# BSU_Comm.net
KiCad netlist of a schematic drawn in Altium Designer
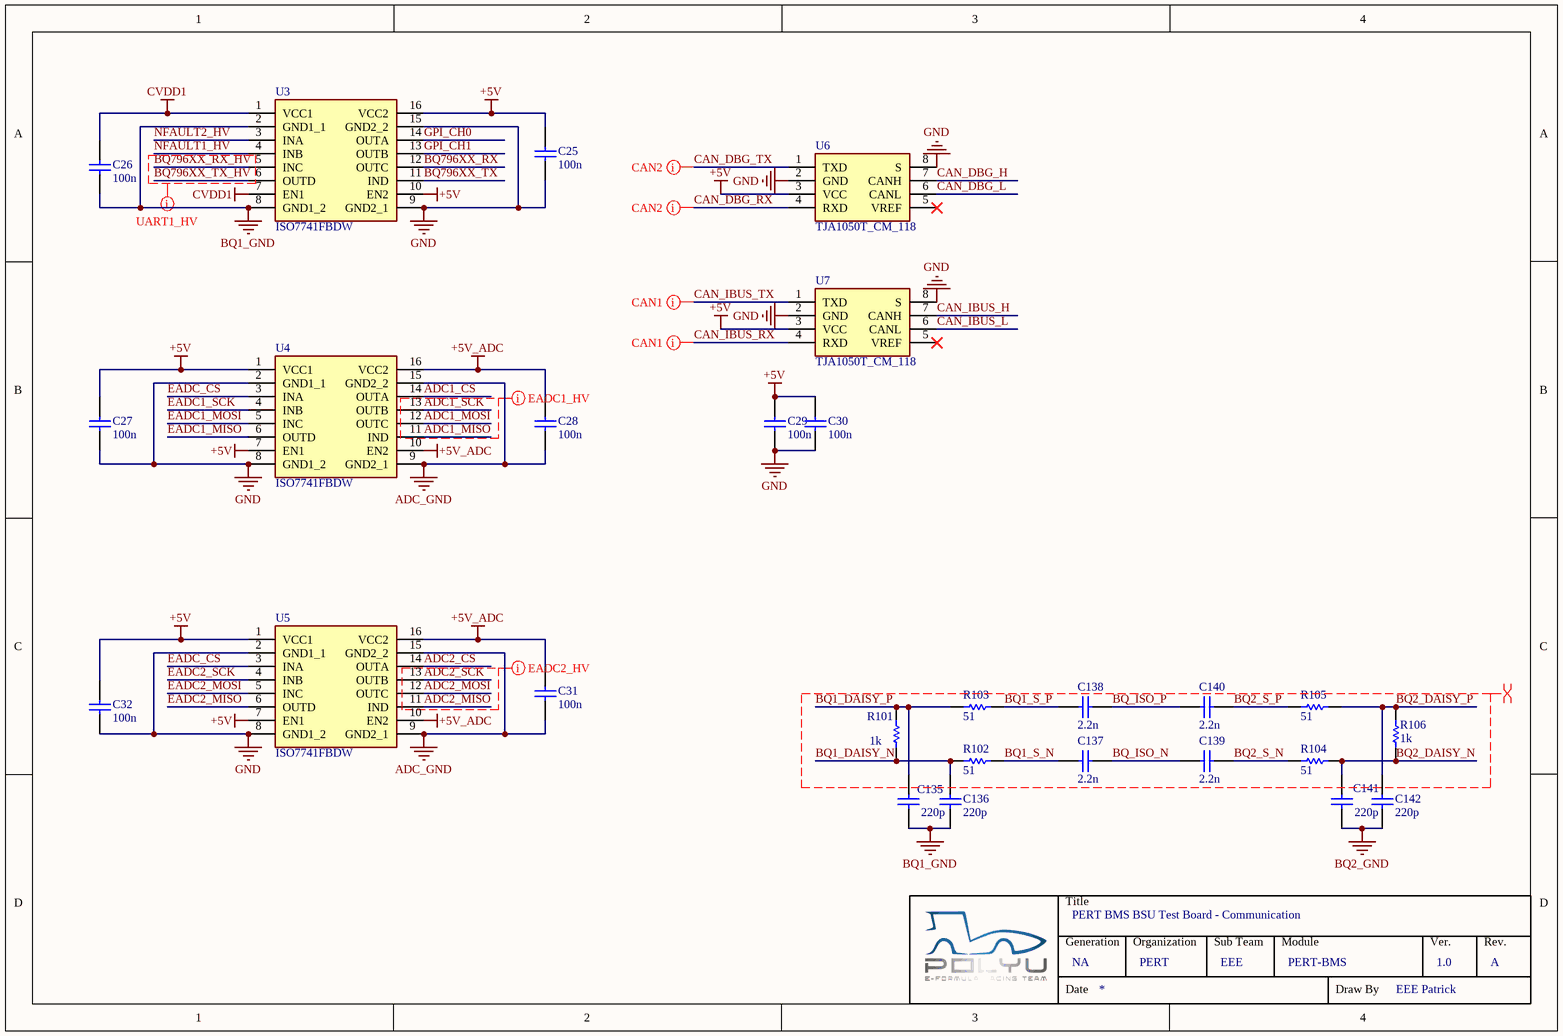
[diagram p0: BSU_Comm.SchDoc]

(export (version "E")
  (design (tool "Eeschema 10.0.6"))
  (components
    (comp (ref "C25")
      (value "100n")
      (footprint "0805_SMD_C")
      (description "0805 SMD Capacitor")
      (libsource (lib "BMS_ShareComponentLibrary") (part "0805_SMD_Capacitor"))
    )
    (comp (ref "C26")
      (value "100n")
      (footprint "0805_SMD_C")
      (description "0805 SMD Capacitor")
      (libsource (lib "BMS_ShareComponentLibrary") (part "0805_SMD_Capacitor"))
    )
    (comp (ref "C27")
      (value "100n")
      (footprint "0805_SMD_C")
      (description "0805 SMD Capacitor")
      (libsource (lib "BMS_ShareComponentLibrary") (part "0805_SMD_Capacitor"))
    )
    (comp (ref "C28")
      (value "100n")
      (footprint "0805_SMD_C")
      (description "0805 SMD Capacitor")
      (libsource (lib "BMS_ShareComponentLibrary") (part "0805_SMD_Capacitor"))
    )
    (comp (ref "C29")
      (value "100n")
      (footprint "0805_SMD_C")
      (description "0805 SMD Capacitor")
      (libsource (lib "BMS_ShareComponentLibrary") (part "0805_SMD_Capacitor"))
    )
    (comp (ref "C30")
      (value "100n")
      (footprint "0805_SMD_C")
      (description "0805 SMD Capacitor")
      (libsource (lib "BMS_ShareComponentLibrary") (part "0805_SMD_Capacitor"))
    )
    (comp (ref "C31")
      (value "100n")
      (footprint "0805_SMD_C")
      (description "0805 SMD Capacitor")
      (libsource (lib "BMS_ShareComponentLibrary") (part "0805_SMD_Capacitor"))
    )
    (comp (ref "C32")
      (value "100n")
      (footprint "0805_SMD_C")
      (description "0805 SMD Capacitor")
      (libsource (lib "BMS_ShareComponentLibrary") (part "0805_SMD_Capacitor"))
    )
    (comp (ref "C135")
      (value "220p")
      (footprint "0603_SMD_C")
      (description "0603 SMD Capacitor")
      (libsource (lib "BMS_ShareComponentLibrary") (part "0603_SMD_Capacitor"))
    )
    (comp (ref "C136")
      (value "220p")
      (footprint "0603_SMD_C")
      (description "0603 SMD Capacitor")
      (libsource (lib "BMS_ShareComponentLibrary") (part "0603_SMD_Capacitor"))
    )
    (comp (ref "C137")
      (value "2.2n")
      (footprint "0603_SMD_C")
      (description "0603 SMD Capacitor")
      (libsource (lib "BMS_ShareComponentLibrary") (part "0603_SMD_Capacitor"))
    )
    (comp (ref "C138")
      (value "2.2n")
      (footprint "0603_SMD_C")
      (description "0603 SMD Capacitor")
      (libsource (lib "BMS_ShareComponentLibrary") (part "0603_SMD_Capacitor"))
    )
    (comp (ref "C139")
      (value "2.2n")
      (footprint "0603_SMD_C")
      (description "0603 SMD Capacitor")
      (libsource (lib "BMS_ShareComponentLibrary") (part "0603_SMD_Capacitor"))
    )
    (comp (ref "C140")
      (value "2.2n")
      (footprint "0603_SMD_C")
      (description "0603 SMD Capacitor")
      (libsource (lib "BMS_ShareComponentLibrary") (part "0603_SMD_Capacitor"))
    )
    (comp (ref "C141")
      (value "220p")
      (footprint "0603_SMD_C")
      (description "0603 SMD Capacitor")
      (libsource (lib "BMS_ShareComponentLibrary") (part "0603_SMD_Capacitor"))
    )
    (comp (ref "C142")
      (value "220p")
      (footprint "0603_SMD_C")
      (description "0603 SMD Capacitor")
      (libsource (lib "BMS_ShareComponentLibrary") (part "0603_SMD_Capacitor"))
    )
    (comp (ref "R101")
      (value "1k")
      (footprint "0603_SMD_R")
      (description "0603 SMD Resistor")
      (libsource (lib "BMS_ShareComponentLibrary") (part "0603_SMD_Resistor"))
    )
    (comp (ref "R102")
      (value "51")
      (footprint "0603_SMD_R")
      (description "0603 SMD Resistor")
      (libsource (lib "BMS_ShareComponentLibrary") (part "0603_SMD_Resistor"))
    )
    (comp (ref "R103")
      (value "51")
      (footprint "0603_SMD_R")
      (description "0603 SMD Resistor")
      (libsource (lib "BMS_ShareComponentLibrary") (part "0603_SMD_Resistor"))
    )
    (comp (ref "R104")
      (value "51")
      (footprint "0603_SMD_R")
      (description "0603 SMD Resistor")
      (libsource (lib "BMS_ShareComponentLibrary") (part "0603_SMD_Resistor"))
    )
    (comp (ref "R105")
      (value "51")
      (footprint "0603_SMD_R")
      (description "0603 SMD Resistor")
      (libsource (lib "BMS_ShareComponentLibrary") (part "0603_SMD_Resistor"))
    )
    (comp (ref "R106")
      (value "1k")
      (footprint "0603_SMD_R")
      (description "0603 SMD Resistor")
      (libsource (lib "BMS_ShareComponentLibrary") (part "0603_SMD_Resistor"))
    )
    (comp (ref "U3")
      (value "ISO7741FBDW")
      (footprint "SOIC16_ISO7741")
      (description "Digital Isolators Robust EMC, quad-channel, 3/1, reinforced digital isolator 16-SOIC -55 to 125")
      (fields (field (name "MOUSER PART NUMBER") "595-ISO7741FBDW"))
      (libsource (lib "BMS_ShareComponentLibrary") (part "ISO7741FBDW"))
    )
    (comp (ref "U4")
      (value "ISO7741FBDW")
      (footprint "SOIC16_ISO7741")
      (description "Digital Isolators Robust EMC, quad-channel, 3/1, reinforced digital isolator 16-SOIC -55 to 125")
      (fields (field (name "MOUSER PART NUMBER") "595-ISO7741FBDW"))
      (libsource (lib "BMS_ShareComponentLibrary") (part "ISO7741FBDW"))
    )
    (comp (ref "U5")
      (value "ISO7741FBDW")
      (footprint "SOIC16_ISO7741")
      (description "Digital Isolators Robust EMC, quad-channel, 3/1, reinforced digital isolator 16-SOIC -55 to 125")
      (fields (field (name "MOUSER PART NUMBER") "595-ISO7741FBDW"))
      (libsource (lib "BMS_ShareComponentLibrary") (part "ISO7741FBDW"))
    )
    (comp (ref "U6")
      (value "TJA1050T_CM_118")
      (footprint "SOIC8_TJA1050")
      (description "NXP - TJA1050T/CM,118 - CAN TRANSCEIVER, 1TX/RX, SOIC-8")
      (fields
        (field (name "MOUSER PART NUMBER") "771-TJA1050T/CM118")
        (field (name "MANUFACTURER_PART_NUMBER") "TJA1050T/CM,118")
      )
      (libsource (lib "BMS_ShareComponentLibrary") (part "TJA1050T"))
    )
    (comp (ref "U7")
      (value "TJA1050T_CM_118")
      (footprint "SOIC8_TJA1050")
      (description "NXP - TJA1050T/CM,118 - CAN TRANSCEIVER, 1TX/RX, SOIC-8")
      (fields
        (field (name "MOUSER PART NUMBER") "771-TJA1050T/CM118")
        (field (name "MANUFACTURER_PART_NUMBER") "TJA1050T/CM,118")
      )
      (libsource (lib "BMS_ShareComponentLibrary") (part "TJA1050T"))
    )
  )
  (nets
    (net (code "1") (name "+5V") (class "Default")
      (node (ref "C25") (pin "2") (pinfunction "2_2") (pintype "passive"))
      (node (ref "C27") (pin "2") (pinfunction "2_2") (pintype "passive"))
      (node (ref "C29") (pin "2") (pinfunction "2_2") (pintype "passive"))
      (node (ref "C30") (pin "2") (pinfunction "2_2") (pintype "passive"))
      (node (ref "C32") (pin "2") (pinfunction "2_2") (pintype "passive"))
      (node (ref "U3") (pin "10") (pinfunction "EN2_10") (pintype "passive"))
      (node (ref "U3") (pin "16") (pinfunction "VCC2_16") (pintype "passive"))
      (node (ref "U4") (pin "1") (pinfunction "VCC1_1") (pintype "passive"))
      (node (ref "U4") (pin "7") (pinfunction "EN1_7") (pintype "passive"))
      (node (ref "U5") (pin "1") (pinfunction "VCC1_1") (pintype "passive"))
      (node (ref "U5") (pin "7") (pinfunction "EN1_7") (pintype "passive"))
      (node (ref "U6") (pin "3") (pinfunction "VCC_3") (pintype "passive"))
      (node (ref "U7") (pin "3") (pinfunction "VCC_3") (pintype "passive"))
    )
    (net (code "2") (name "+5V_ADC") (class "Default")
      (node (ref "C28") (pin "2") (pinfunction "2_2") (pintype "passive"))
      (node (ref "C31") (pin "2") (pinfunction "2_2") (pintype "passive"))
      (node (ref "U4") (pin "10") (pinfunction "EN2_10") (pintype "passive"))
      (node (ref "U4") (pin "16") (pinfunction "VCC2_16") (pintype "passive"))
      (node (ref "U5") (pin "10") (pinfunction "EN2_10") (pintype "passive"))
      (node (ref "U5") (pin "16") (pinfunction "VCC2_16") (pintype "passive"))
    )
    (net (code "3") (name "/ADC1_CS") (class "Default")
      (node (ref "U4") (pin "14") (pinfunction "OUTA_14") (pintype "passive"))
    )
    (net (code "4") (name "/ADC1_MISO") (class "Default")
      (node (ref "U4") (pin "11") (pinfunction "IND_11") (pintype "passive"))
    )
    (net (code "5") (name "/ADC1_MOSI") (class "Default")
      (node (ref "U4") (pin "12") (pinfunction "OUTC_12") (pintype "passive"))
    )
    (net (code "6") (name "/ADC1_SCK") (class "Default")
      (node (ref "U4") (pin "13") (pinfunction "OUTB_13") (pintype "passive"))
    )
    (net (code "7") (name "/ADC2_CS") (class "Default")
      (node (ref "U5") (pin "14") (pinfunction "OUTA_14") (pintype "passive"))
    )
    (net (code "8") (name "/ADC2_MISO") (class "Default")
      (node (ref "U5") (pin "11") (pinfunction "IND_11") (pintype "passive"))
    )
    (net (code "9") (name "/ADC2_MOSI") (class "Default")
      (node (ref "U5") (pin "12") (pinfunction "OUTC_12") (pintype "passive"))
    )
    (net (code "10") (name "/ADC2_SCK") (class "Default")
      (node (ref "U5") (pin "13") (pinfunction "OUTB_13") (pintype "passive"))
    )
    (net (code "11") (name "/BQ1_DAISY_N") (class "Default")
      (node (ref "C136") (pin "2") (pinfunction "2_2") (pintype "passive"))
      (node (ref "R101") (pin "2") (pinfunction "2_2") (pintype "passive"))
      (node (ref "R102") (pin "2") (pinfunction "2_2") (pintype "passive"))
    )
    (net (code "12") (name "/BQ1_DAISY_P") (class "Default")
      (node (ref "C135") (pin "2") (pinfunction "2_2") (pintype "passive"))
      (node (ref "R101") (pin "1") (pinfunction "1_1") (pintype "passive"))
      (node (ref "R103") (pin "2") (pinfunction "2_2") (pintype "passive"))
    )
    (net (code "13") (name "/BQ1_S_N") (class "Default")
      (node (ref "C137") (pin "2") (pinfunction "2_2") (pintype "passive"))
      (node (ref "R102") (pin "1") (pinfunction "1_1") (pintype "passive"))
    )
    (net (code "14") (name "/BQ1_S_P") (class "Default")
      (node (ref "C138") (pin "2") (pinfunction "2_2") (pintype "passive"))
      (node (ref "R103") (pin "1") (pinfunction "1_1") (pintype "passive"))
    )
    (net (code "15") (name "/BQ2_DAISY_N") (class "Default")
      (node (ref "C141") (pin "2") (pinfunction "2_2") (pintype "passive"))
      (node (ref "R104") (pin "2") (pinfunction "2_2") (pintype "passive"))
      (node (ref "R106") (pin "1") (pinfunction "1_1") (pintype "passive"))
    )
    (net (code "16") (name "/BQ2_DAISY_P") (class "Default")
      (node (ref "C142") (pin "2") (pinfunction "2_2") (pintype "passive"))
      (node (ref "R105") (pin "2") (pinfunction "2_2") (pintype "passive"))
      (node (ref "R106") (pin "2") (pinfunction "2_2") (pintype "passive"))
    )
    (net (code "17") (name "/BQ2_S_N") (class "Default")
      (node (ref "C139") (pin "2") (pinfunction "2_2") (pintype "passive"))
      (node (ref "R104") (pin "1") (pinfunction "1_1") (pintype "passive"))
    )
    (net (code "18") (name "/BQ2_S_P") (class "Default")
      (node (ref "C140") (pin "2") (pinfunction "2_2") (pintype "passive"))
      (node (ref "R105") (pin "1") (pinfunction "1_1") (pintype "passive"))
    )
    (net (code "19") (name "/BQ796XX_RX") (class "Default")
      (node (ref "U3") (pin "12") (pinfunction "OUTC_12") (pintype "passive"))
    )
    (net (code "20") (name "/BQ796XX_RX_HV") (class "Default")
      (node (ref "U3") (pin "5") (pinfunction "INC_5") (pintype "passive"))
    )
    (net (code "21") (name "/BQ796XX_TX") (class "Default")
      (node (ref "U3") (pin "11") (pinfunction "IND_11") (pintype "passive"))
    )
    (net (code "22") (name "/BQ796XX_TX_HV") (class "Default")
      (node (ref "U3") (pin "6") (pinfunction "OUTD_6") (pintype "passive"))
    )
    (net (code "23") (name "/BQ_ISO_N") (class "Default")
      (node (ref "C137") (pin "1") (pinfunction "1_1") (pintype "passive"))
      (node (ref "C139") (pin "1") (pinfunction "1_1") (pintype "passive"))
    )
    (net (code "24") (name "/BQ_ISO_P") (class "Default")
      (node (ref "C138") (pin "1") (pinfunction "1_1") (pintype "passive"))
      (node (ref "C140") (pin "1") (pinfunction "1_1") (pintype "passive"))
    )
    (net (code "25") (name "/CAN_DBG_H") (class "Default")
      (node (ref "U6") (pin "7") (pinfunction "CANH_7") (pintype "passive"))
    )
    (net (code "26") (name "/CAN_DBG_L") (class "Default")
      (node (ref "U6") (pin "6") (pinfunction "CANL_6") (pintype "passive"))
    )
    (net (code "27") (name "/CAN_DBG_RX") (class "Default")
      (node (ref "U6") (pin "4") (pinfunction "RXD_4") (pintype "passive"))
    )
    (net (code "28") (name "/CAN_DBG_TX") (class "Default")
      (node (ref "U6") (pin "1") (pinfunction "TXD_1") (pintype "passive"))
    )
    (net (code "29") (name "/CAN_IBUS_H") (class "Default")
      (node (ref "U7") (pin "7") (pinfunction "CANH_7") (pintype "passive"))
    )
    (net (code "30") (name "/CAN_IBUS_L") (class "Default")
      (node (ref "U7") (pin "6") (pinfunction "CANL_6") (pintype "passive"))
    )
    (net (code "31") (name "/CAN_IBUS_RX") (class "Default")
      (node (ref "U7") (pin "4") (pinfunction "RXD_4") (pintype "passive"))
    )
    (net (code "32") (name "/CAN_IBUS_TX") (class "Default")
      (node (ref "U7") (pin "1") (pinfunction "TXD_1") (pintype "passive"))
    )
    (net (code "33") (name "/EADC1_MISO") (class "Default")
      (node (ref "U4") (pin "6") (pinfunction "OUTD_6") (pintype "passive"))
    )
    (net (code "34") (name "/EADC1_MOSI") (class "Default")
      (node (ref "U4") (pin "5") (pinfunction "INC_5") (pintype "passive"))
    )
    (net (code "35") (name "/EADC1_SCK") (class "Default")
      (node (ref "U4") (pin "4") (pinfunction "INB_4") (pintype "passive"))
    )
    (net (code "36") (name "/EADC2_MISO") (class "Default")
      (node (ref "U5") (pin "6") (pinfunction "OUTD_6") (pintype "passive"))
    )
    (net (code "37") (name "/EADC2_MOSI") (class "Default")
      (node (ref "U5") (pin "5") (pinfunction "INC_5") (pintype "passive"))
    )
    (net (code "38") (name "/EADC2_SCK") (class "Default")
      (node (ref "U5") (pin "4") (pinfunction "INB_4") (pintype "passive"))
    )
    (net (code "39") (name "/EADC_CS") (class "Default")
      (node (ref "U4") (pin "3") (pinfunction "INA_3") (pintype "passive"))
      (node (ref "U5") (pin "3") (pinfunction "INA_3") (pintype "passive"))
    )
    (net (code "40") (name "/GPI_CH0") (class "Default")
      (node (ref "U3") (pin "14") (pinfunction "OUTA_14") (pintype "passive"))
    )
    (net (code "41") (name "/GPI_CH1") (class "Default")
      (node (ref "U3") (pin "13") (pinfunction "OUTB_13") (pintype "passive"))
    )
    (net (code "42") (name "/NFAULT1_HV") (class "Default")
      (node (ref "U3") (pin "4") (pinfunction "INB_4") (pintype "passive"))
    )
    (net (code "43") (name "/NFAULT2_HV") (class "Default")
      (node (ref "U3") (pin "3") (pinfunction "INA_3") (pintype "passive"))
    )
    (net (code "44") (name "ADC_GND") (class "Default")
      (node (ref "C28") (pin "1") (pinfunction "1_1") (pintype "passive"))
      (node (ref "C31") (pin "1") (pinfunction "1_1") (pintype "passive"))
      (node (ref "U4") (pin "15") (pinfunction "GND2_2_15") (pintype "passive"))
      (node (ref "U4") (pin "9") (pinfunction "GND2_1_9") (pintype "passive"))
      (node (ref "U5") (pin "15") (pinfunction "GND2_2_15") (pintype "passive"))
      (node (ref "U5") (pin "9") (pinfunction "GND2_1_9") (pintype "passive"))
    )
    (net (code "45") (name "BQ1_GND") (class "Default")
      (node (ref "C135") (pin "1") (pinfunction "1_1") (pintype "passive"))
      (node (ref "C136") (pin "1") (pinfunction "1_1") (pintype "passive"))
      (node (ref "C26") (pin "1") (pinfunction "1_1") (pintype "passive"))
      (node (ref "U3") (pin "2") (pinfunction "GND1_1_2") (pintype "passive"))
      (node (ref "U3") (pin "8") (pinfunction "GND1_2_8") (pintype "passive"))
    )
    (net (code "46") (name "BQ2_GND") (class "Default")
      (node (ref "C141") (pin "1") (pinfunction "1_1") (pintype "passive"))
      (node (ref "C142") (pin "1") (pinfunction "1_1") (pintype "passive"))
    )
    (net (code "47") (name "CVDD1") (class "Default")
      (node (ref "C26") (pin "2") (pinfunction "2_2") (pintype "passive"))
      (node (ref "U3") (pin "1") (pinfunction "VCC1_1") (pintype "passive"))
      (node (ref "U3") (pin "7") (pinfunction "EN1_7") (pintype "passive"))
    )
    (net (code "48") (name "GND") (class "Default")
      (node (ref "C25") (pin "1") (pinfunction "1_1") (pintype "passive"))
      (node (ref "C27") (pin "1") (pinfunction "1_1") (pintype "passive"))
      (node (ref "C29") (pin "1") (pinfunction "1_1") (pintype "passive"))
      (node (ref "C30") (pin "1") (pinfunction "1_1") (pintype "passive"))
      (node (ref "C32") (pin "1") (pinfunction "1_1") (pintype "passive"))
      (node (ref "U3") (pin "15") (pinfunction "GND2_2_15") (pintype "passive"))
      (node (ref "U3") (pin "9") (pinfunction "GND2_1_9") (pintype "passive"))
      (node (ref "U4") (pin "2") (pinfunction "GND1_1_2") (pintype "passive"))
      (node (ref "U4") (pin "8") (pinfunction "GND1_2_8") (pintype "passive"))
      (node (ref "U5") (pin "2") (pinfunction "GND1_1_2") (pintype "passive"))
      (node (ref "U5") (pin "8") (pinfunction "GND1_2_8") (pintype "passive"))
      (node (ref "U6") (pin "2") (pinfunction "GND_2") (pintype "passive"))
      (node (ref "U6") (pin "8") (pinfunction "S_8") (pintype "passive"))
      (node (ref "U7") (pin "2") (pinfunction "GND_2") (pintype "passive"))
      (node (ref "U7") (pin "8") (pinfunction "S_8") (pintype "passive"))
    )
    (net (code "49") (name "unconnected-(U6-VREF-Pad5)") (class "Default")
      (node (ref "U6") (pin "5") (pinfunction "VREF_5") (pintype "passive+no_connect"))
    )
    (net (code "50") (name "unconnected-(U7-VREF-Pad5)") (class "Default")
      (node (ref "U7") (pin "5") (pinfunction "VREF_5") (pintype "passive+no_connect"))
    )
  )
)
